# Read_Time_sensor_Tho_AMT_V2_0.net
KiCad netlist of a schematic drawn in Altium Designer
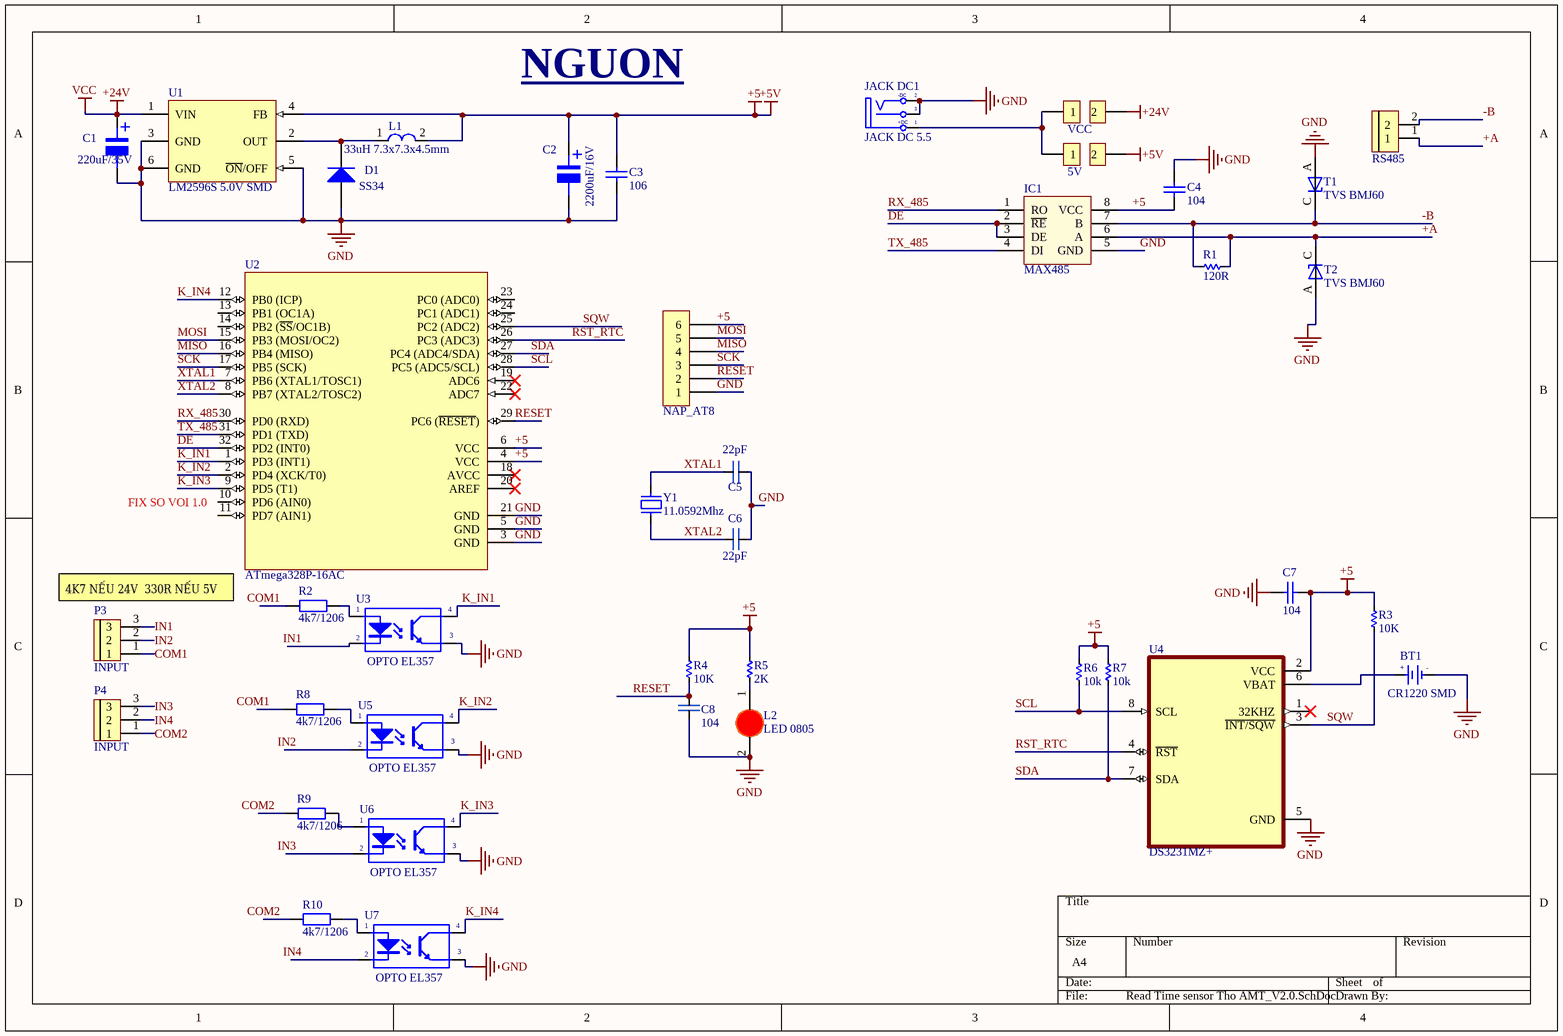
[diagram p0: Read Time sensor Tho AMT_V2.0.SchDoc]

(export (version "E")
  (design (tool "Eeschema 10.0.6"))
  (components
    (comp (ref "BT1")
      (value "CR1220 SMD")
      (footprint "DE PIN CR1220")
      (libsource (lib "NGUYEN VAN ANH HaUI") (part "De pin CR1220 SMD"))
    )
    (comp (ref "C1")
      (value "220uF/35V")
      (footprint "tu nhom 10 (g)")
      (description "Dán 35V")
      (libsource (lib "Altium_Lib_by_KhueNguyenCreator") (part "Tu Nhom 220uF 50V"))
    )
    (comp (ref "C2")
      (value "2200uF/16V")
      (footprint "tu nhom 6.3 (d)")
      (description "Dán")
      (libsource (lib "Altium_Lib_by_KhueNguyenCreator") (part "Tu Nhom 10uF 20V"))
    )
    (comp (ref "C3")
      (value "106")
      (footprint "tu 0805")
      (description "Dán")
      (libsource (lib "Altium_Lib_by_KhueNguyenCreator") (part "Tu 0805 105 50V 10%"))
    )
    (comp (ref "C4")
      (value "104")
      (footprint "TU 0805")
      (description "Dán")
      (libsource (lib "Altium_Lib_by_KhueNguyenCreator") (part "Tu 0805 104 50V 10%"))
    )
    (comp (ref "C5")
      (value "22pF")
      (footprint "TU 0805")
      (libsource (lib "NGUYEN VAN ANH HaUI") (part "TU 0805"))
    )
    (comp (ref "C6")
      (value "22pF")
      (footprint "TU 0805")
      (libsource (lib "NGUYEN VAN ANH HaUI") (part "TU 0805"))
    )
    (comp (ref "C7")
      (value "104")
      (footprint "TU 0805")
      (description "Dán")
      (libsource (lib "Altium_Lib_by_KhueNguyenCreator") (part "Tu 0805 104 50V 10%"))
    )
    (comp (ref "C8")
      (value "104")
      (footprint "TU 0805")
      (libsource (lib "NGUYEN VAN ANH HaUI") (part "TU 0805"))
    )
    (comp (ref "D1")
      (value "SS34")
      (footprint "DIODE SMA")
      (description "Dán")
      (libsource (lib "Altium_Lib_by_KhueNguyenCreator") (part "Diode SS14 ( 1N5819)"))
    )
    (comp (ref "EDG 1")
      (value "RS485")
      (footprint "CON 2 2EDG5.08")
      (description "Cắm")
      (libsource (lib "Altium_Lib_by_KhueNguyenCreator") (part "CON 2 EDG5.08"))
    )
    (comp (ref "H1")
      (value "NAP_AT8")
      (footprint "Header 6P DC 2.54")
      (description "Cắm")
      (libsource (lib "Altium_Lib_by_KhueNguyenCreator") (part "Header 6P 2.54 Duc Cong"))
    )
    (comp (ref "IC1")
      (value "MAX485")
      (footprint "SO8")
      (description "RS232 - RS485 (Same sn75176)")
      (libsource (lib "Cty1") (part "MAX485"))
    )
    (comp (ref "JACK DC1")
      (value "JACK DC 5.5")
      (footprint "JACK DC 5.5")
      (libsource (lib "NGUYEN VAN ANH HaUI") (part "JACK DC 5.5"))
    )
    (comp (ref "L1")
      (value "33uH 7.3x7.3x4.5mm")
      (footprint "L-SMD-M-7.3x4.5")
      (fields
        (field (name "PARTNO") "78477010")
        (field (name "MANUFACTURER") "Wurth Elektronik")
        (field (name "CREATED BY") "Baojun Chen")
      )
      (libsource (lib "NGUYEN VAN ANH HaUI") (part "L-SMD-1"))
    )
    (comp (ref "L2")
      (value "LED 0805")
      (footprint "LED-0805-Red")
      (description "Dán")
      (libsource (lib "Altium_Lib_by_KhueNguyenCreator") (part "LED 0805 Do"))
    )
    (comp (ref "P1")
      (value "VCC")
      (footprint "SMT-0805-RES")
      (libsource (lib "NGUYEN VAN ANH HaUI") (part "Pad han noi 2 duong"))
    )
    (comp (ref "P2")
      (value "5V")
      (footprint "SMT-0805-RES")
      (libsource (lib "NGUYEN VAN ANH HaUI") (part "Pad han noi 2 duong"))
    )
    (comp (ref "P3")
      (value "INPUT")
      (footprint "CON 3 3EDG5.08")
      (description "Cắm")
      (libsource (lib "NGUYEN VAN ANH HaUI") (part "CON 3 EDG5.08"))
    )
    (comp (ref "P4")
      (value "INPUT")
      (footprint "CON 3 3EDG5.08")
      (description "Cắm")
      (libsource (lib "NGUYEN VAN ANH HaUI") (part "CON 3 EDG5.08"))
    )
    (comp (ref "R1")
      (value "120R")
      (footprint "RES-SMD-0805")
      (description "Resistor")
      (fields
        (field (name "MANUFACTURER") "Generic Components")
        (field (name "PUBLISHER") "Altium Hobart Technology Centre")
      )
      (libsource (lib "NGUYEN VAN ANH HaUI") (part "Res-SMD"))
    )
    (comp (ref "R2")
      (value "4k7/1206")
      (footprint "tro smd 1206")
      (description "Dán")
      (libsource (lib "NGUYEN VAN ANH HaUI") (part "Tro 0805 5% 10k"))
    )
    (comp (ref "R3")
      (value "10K")
      (footprint "RES-SMD-0805")
      (description "Resistor")
      (fields
        (field (name "MANUFACTURER") "Generic Components")
        (field (name "PUBLISHER") "Altium Hobart Technology Centre")
      )
      (libsource (lib "NGUYEN VAN ANH HaUI") (part "Res-SMD"))
    )
    (comp (ref "R4")
      (value "10K")
      (footprint "RES-SMD-0805")
      (description "Resistor")
      (fields
        (field (name "MANUFACTURER") "Generic Components")
        (field (name "PUBLISHER") "Altium Hobart Technology Centre")
      )
      (libsource (lib "NGUYEN VAN ANH HaUI") (part "Res-SMD"))
    )
    (comp (ref "R5")
      (value "2K")
      (footprint "RES-SMD-0805")
      (description "Resistor")
      (fields
        (field (name "MANUFACTURER") "Generic Components")
        (field (name "PUBLISHER") "Altium Hobart Technology Centre")
      )
      (libsource (lib "NGUYEN VAN ANH HaUI") (part "Res-SMD"))
    )
    (comp (ref "R6")
      (value "10k")
      (footprint "RES-SMD-0805")
      (description "Resistor")
      (fields
        (field (name "MANUFACTURER") "Generic Components")
        (field (name "PUBLISHER") "Altium Hobart Technology Centre")
      )
      (libsource (lib "NGUYEN VAN ANH HaUI") (part "Res-SMD"))
    )
    (comp (ref "R7")
      (value "10k")
      (footprint "RES-SMD-0805")
      (description "Resistor")
      (fields
        (field (name "MANUFACTURER") "Generic Components")
        (field (name "PUBLISHER") "Altium Hobart Technology Centre")
      )
      (libsource (lib "NGUYEN VAN ANH HaUI") (part "Res-SMD"))
    )
    (comp (ref "R8")
      (value "4k7/1206")
      (footprint "tro smd 1206")
      (description "Dán")
      (libsource (lib "NGUYEN VAN ANH HaUI") (part "Tro 0805 5% 10k"))
    )
    (comp (ref "R9")
      (value "4k7/1206")
      (footprint "tro smd 1206")
      (description "Dán")
      (libsource (lib "NGUYEN VAN ANH HaUI") (part "Tro 0805 5% 10k"))
    )
    (comp (ref "R10")
      (value "4k7/1206")
      (footprint "tro smd 1206")
      (description "Dán")
      (libsource (lib "NGUYEN VAN ANH HaUI") (part "Tro 0805 5% 10k"))
    )
    (comp (ref "T1")
      (value "TVS BMJ60")
      (footprint "TVS BMJ60")
      (libsource (lib "NGUYEN VAN ANH HaUI") (part "TVS BMJ60"))
    )
    (comp (ref "T2")
      (value "TVS BMJ60")
      (footprint "TVS BMJ60")
      (libsource (lib "NGUYEN VAN ANH HaUI") (part "TVS BMJ60"))
    )
    (comp (ref "U1")
      (value "LM2596S 5.0V SMD")
      (footprint "TO263-5")
      (description "Dán")
      (libsource (lib "Altium_Lib_by_KhueNguyenCreator") (part "LM2576HVS 5.0V SMD"))
    )
    (comp (ref "U2")
      (value "ATmega328P-16AC")
      (footprint "32A_N")
      (description "8-Bit AVR Microcontroller with 8K Bytes of In-System Programmable Flash Memory")
      (fields (field (name "PUBLISHER") "Altium Limited"))
      (libsource (lib "Atmel Microcontroller 8-Bit AVR") (part "ATmega8-16AC"))
    )
    (comp (ref "U3")
      (value "OPTO EL357")
      (footprint "OPTO EL354")
      (description "Single Opto")
      (libsource (lib "NGUYEN VAN ANH HaUI") (part "OPTO PC817 SMD"))
    )
    (comp (ref "U4")
      (value "DS3231MZ+")
      (footprint "SOIC-8")
      (fields (field (name "MF") "Analog Devices"))
      (libsource (lib "VIN_HW") (part "DS3231MZ+"))
    )
    (comp (ref "U5")
      (value "OPTO EL357")
      (footprint "OPTO EL354")
      (description "Single Opto")
      (libsource (lib "NGUYEN VAN ANH HaUI") (part "OPTO PC817 SMD"))
    )
    (comp (ref "U6")
      (value "OPTO EL357")
      (footprint "OPTO EL354")
      (description "Single Opto")
      (libsource (lib "NGUYEN VAN ANH HaUI") (part "OPTO PC817 SMD"))
    )
    (comp (ref "U7")
      (value "OPTO EL357")
      (footprint "OPTO EL354")
      (description "Single Opto")
      (libsource (lib "NGUYEN VAN ANH HaUI") (part "OPTO PC817 SMD"))
    )
    (comp (ref "Y1")
      (value "11.0592Mhz")
      (footprint "Thach Anh 2 chan SMD5032")
      (description "Crystal For all Crystal 2pin.")
      (libsource (lib "NGUYEN VAN ANH HaUI") (part "Thach Anh 2 chan SMD 5032"))
    )
  )
  (nets
    (net (code "1") (name "+5") (class "Default")
      (node (ref "C2") (pin "1") (pinfunction "1_1") (pintype "passive"))
      (node (ref "C3") (pin "2") (pinfunction "2_2") (pintype "passive"))
      (node (ref "C4") (pin "1") (pinfunction "1_1") (pintype "passive"))
      (node (ref "C7") (pin "1") (pinfunction "1_1") (pintype "passive"))
      (node (ref "H1") (pin "6") (pinfunction "6_6") (pintype "passive"))
      (node (ref "IC1") (pin "8") (pinfunction "VCC_8") (pintype "passive"))
      (node (ref "L1") (pin "2") (pinfunction "2_2") (pintype "passive"))
      (node (ref "P2") (pin "2") (pinfunction "2_2") (pintype "passive"))
      (node (ref "R3") (pin "1") (pinfunction "1_1") (pintype "passive"))
      (node (ref "R4") (pin "2") (pinfunction "2_2") (pintype "passive"))
      (node (ref "R5") (pin "1") (pinfunction "1_1") (pintype "passive"))
      (node (ref "R6") (pin "1") (pinfunction "1_1") (pintype "passive"))
      (node (ref "R7") (pin "1") (pinfunction "1_1") (pintype "passive"))
      (node (ref "U1") (pin "4") (pinfunction "FB_4") (pintype "input"))
      (node (ref "U2") (pin "4") (pinfunction "VCC_4") (pintype "power_in"))
      (node (ref "U2") (pin "6") (pinfunction "VCC_6") (pintype "power_in"))
      (node (ref "U4") (pin "2") (pinfunction "VCC_2") (pintype "power_in"))
    )
    (net (code "2") (name "+24V") (class "Default")
      (node (ref "C1") (pin "1") (pinfunction "1_1") (pintype "passive"))
      (node (ref "P1") (pin "2") (pinfunction "2_2") (pintype "passive"))
      (node (ref "U1") (pin "1") (pinfunction "VIN_1") (pintype "power_in"))
    )
    (net (code "3") (name "/+A") (class "Default")
      (node (ref "EDG 1") (pin "1") (pinfunction "1_1") (pintype "passive"))
      (node (ref "IC1") (pin "6") (pinfunction "A_6") (pintype "passive"))
      (node (ref "R1") (pin "2") (pinfunction "2_2") (pintype "passive"))
      (node (ref "T2") (pin "C") (pinfunction "C_C") (pintype "passive"))
    )
    (net (code "4") (name "/-B") (class "Default")
      (node (ref "EDG 1") (pin "2") (pinfunction "2_2") (pintype "passive"))
      (node (ref "IC1") (pin "7") (pinfunction "B_7") (pintype "passive"))
      (node (ref "R1") (pin "1") (pinfunction "1_1") (pintype "passive"))
      (node (ref "T1") (pin "C") (pinfunction "C_C") (pintype "passive"))
    )
    (net (code "5") (name "/COM1") (class "Default")
      (node (ref "P3") (pin "1") (pinfunction "1_1") (pintype "passive"))
      (node (ref "R2") (pin "1") (pinfunction "1_1") (pintype "passive"))
      (node (ref "R8") (pin "1") (pinfunction "1_1") (pintype "passive"))
    )
    (net (code "6") (name "/COM2") (class "Default")
      (node (ref "P4") (pin "1") (pinfunction "1_1") (pintype "passive"))
      (node (ref "R10") (pin "1") (pinfunction "1_1") (pintype "passive"))
      (node (ref "R9") (pin "1") (pinfunction "1_1") (pintype "passive"))
    )
    (net (code "7") (name "/DE") (class "Default")
      (node (ref "IC1") (pin "2") (pinfunction "~{RE}_2") (pintype "passive"))
      (node (ref "IC1") (pin "3") (pinfunction "DE_3") (pintype "passive"))
      (node (ref "U2") (pin "32") (pinfunction "PD2_(INT0)_32") (pintype "bidirectional"))
    )
    (net (code "8") (name "/IN1") (class "Default")
      (node (ref "P3") (pin "3") (pinfunction "3_3") (pintype "passive"))
      (node (ref "U3") (pin "2") (pinfunction "K_2") (pintype "passive"))
    )
    (net (code "9") (name "/IN2") (class "Default")
      (node (ref "P3") (pin "2") (pinfunction "2_2") (pintype "passive"))
      (node (ref "U5") (pin "2") (pinfunction "K_2") (pintype "passive"))
    )
    (net (code "10") (name "/IN3") (class "Default")
      (node (ref "P4") (pin "3") (pinfunction "3_3") (pintype "passive"))
      (node (ref "U6") (pin "2") (pinfunction "K_2") (pintype "passive"))
    )
    (net (code "11") (name "/IN4") (class "Default")
      (node (ref "P4") (pin "2") (pinfunction "2_2") (pintype "passive"))
      (node (ref "U7") (pin "2") (pinfunction "K_2") (pintype "passive"))
    )
    (net (code "12") (name "/K_IN1") (class "Default")
      (node (ref "U2") (pin "1") (pinfunction "PD3_(INT1)_1") (pintype "bidirectional"))
      (node (ref "U3") (pin "4") (pinfunction "C_4") (pintype "passive"))
    )
    (net (code "13") (name "/K_IN2") (class "Default")
      (node (ref "U2") (pin "2") (pinfunction "PD4_(XCK/T0)_2") (pintype "bidirectional"))
      (node (ref "U5") (pin "4") (pinfunction "C_4") (pintype "passive"))
    )
    (net (code "14") (name "/K_IN3") (class "Default")
      (node (ref "U2") (pin "9") (pinfunction "PD5_(T1)_9") (pintype "bidirectional"))
      (node (ref "U6") (pin "4") (pinfunction "C_4") (pintype "passive"))
    )
    (net (code "15") (name "/K_IN4") (class "Default")
      (node (ref "U2") (pin "12") (pinfunction "PB0_(ICP)_12") (pintype "bidirectional"))
      (node (ref "U7") (pin "4") (pinfunction "C_4") (pintype "passive"))
    )
    (net (code "16") (name "/MISO") (class "Default")
      (node (ref "H1") (pin "4") (pinfunction "4_4") (pintype "passive"))
      (node (ref "U2") (pin "16") (pinfunction "PB4_(MISO)_16") (pintype "bidirectional"))
    )
    (net (code "17") (name "/MOSI") (class "Default")
      (node (ref "H1") (pin "5") (pinfunction "5_5") (pintype "passive"))
      (node (ref "U2") (pin "15") (pinfunction "PB3_(MOSI/OC2)_15") (pintype "bidirectional"))
    )
    (net (code "18") (name "/RESET") (class "Default")
      (node (ref "C8") (pin "1") (pinfunction "33_1") (pintype "passive"))
      (node (ref "H1") (pin "2") (pinfunction "2_2") (pintype "passive"))
      (node (ref "R4") (pin "1") (pinfunction "1_1") (pintype "passive"))
      (node (ref "U2") (pin "29") (pinfunction "PC6_(~{RESET})_29") (pintype "bidirectional"))
    )
    (net (code "19") (name "/RST_RTC") (class "Default")
      (node (ref "U2") (pin "26") (pinfunction "PC3_(ADC3)_26") (pintype "bidirectional"))
      (node (ref "U4") (pin "4") (pinfunction "~{RST}_4") (pintype "bidirectional"))
    )
    (net (code "20") (name "/RX_485") (class "Default")
      (node (ref "IC1") (pin "1") (pinfunction "RO_1") (pintype "passive"))
      (node (ref "U2") (pin "30") (pinfunction "PD0_(RXD)_30") (pintype "bidirectional"))
    )
    (net (code "21") (name "/SCK") (class "Default")
      (node (ref "H1") (pin "3") (pinfunction "3_3") (pintype "passive"))
      (node (ref "U2") (pin "17") (pinfunction "PB5_(SCK)_17") (pintype "bidirectional"))
    )
    (net (code "22") (name "/SCL") (class "Default")
      (node (ref "R6") (pin "2") (pinfunction "2_2") (pintype "passive"))
      (node (ref "U2") (pin "28") (pinfunction "PC5_(ADC5/SCL)_28") (pintype "bidirectional"))
      (node (ref "U4") (pin "8") (pinfunction "SCL_8") (pintype "input"))
    )
    (net (code "23") (name "/SDA") (class "Default")
      (node (ref "R7") (pin "2") (pinfunction "2_2") (pintype "passive"))
      (node (ref "U2") (pin "27") (pinfunction "PC4_(ADC4/SDA)_27") (pintype "bidirectional"))
      (node (ref "U4") (pin "7") (pinfunction "SDA_7") (pintype "bidirectional"))
    )
    (net (code "24") (name "/SQW") (class "Default")
      (node (ref "R3") (pin "2") (pinfunction "2_2") (pintype "passive"))
      (node (ref "U2") (pin "25") (pinfunction "PC2_(ADC2)_25") (pintype "bidirectional"))
      (node (ref "U4") (pin "3") (pinfunction "~{INT/SQW}_3") (pintype "output"))
    )
    (net (code "25") (name "/TX_485") (class "Default")
      (node (ref "IC1") (pin "4") (pinfunction "DI_4") (pintype "passive"))
      (node (ref "U2") (pin "31") (pinfunction "PD1_(TXD)_31") (pintype "bidirectional"))
    )
    (net (code "26") (name "/XTAL1") (class "Default")
      (node (ref "C5") (pin "1") (pinfunction "33_1") (pintype "passive"))
      (node (ref "U2") (pin "7") (pinfunction "PB6_(XTAL1/TOSC1)_7") (pintype "bidirectional"))
      (node (ref "Y1") (pin "2") (pinfunction "2_2") (pintype "passive"))
    )
    (net (code "27") (name "/XTAL2") (class "Default")
      (node (ref "C6") (pin "1") (pinfunction "33_1") (pintype "passive"))
      (node (ref "U2") (pin "8") (pinfunction "PB7_(XTAL2/TOSC2)_8") (pintype "bidirectional"))
      (node (ref "Y1") (pin "1") (pinfunction "1_1") (pintype "passive"))
    )
    (net (code "28") (name "GND") (class "Default")
      (node (ref "BT1") (pin "2") (pinfunction "GND_2") (pintype "passive"))
      (node (ref "C1") (pin "2") (pinfunction "2_2") (pintype "passive"))
      (node (ref "C2") (pin "2") (pinfunction "2_2") (pintype "passive"))
      (node (ref "C3") (pin "1") (pinfunction "1_1") (pintype "passive"))
      (node (ref "C4") (pin "2") (pinfunction "2_2") (pintype "passive"))
      (node (ref "C5") (pin "2") (pinfunction "2_2") (pintype "passive"))
      (node (ref "C6") (pin "2") (pinfunction "2_2") (pintype "passive"))
      (node (ref "C7") (pin "2") (pinfunction "2_2") (pintype "passive"))
      (node (ref "C8") (pin "2") (pinfunction "2_2") (pintype "passive"))
      (node (ref "D1") (pin "1") (pinfunction "A_1") (pintype "passive"))
      (node (ref "H1") (pin "1") (pinfunction "1_1") (pintype "passive"))
      (node (ref "IC1") (pin "5") (pinfunction "GND_5") (pintype "passive"))
      (node (ref "JACK DC1") (pin "2") (pinfunction "TN_2") (pintype "passive"))
      (node (ref "JACK DC1") (pin "3") (pinfunction "S_3") (pintype "power_in"))
      (node (ref "L2") (pin "2") (pinfunction "K_2") (pintype "passive"))
      (node (ref "T1") (pin "A") (pinfunction "A_A") (pintype "passive"))
      (node (ref "T2") (pin "A") (pinfunction "A_A") (pintype "passive"))
      (node (ref "U1") (pin "3") (pinfunction "GND_3") (pintype "power_in"))
      (node (ref "U1") (pin "5") (pinfunction "~{ON}/OFF_5") (pintype "input"))
      (node (ref "U1") (pin "6") (pinfunction "GND_6") (pintype "passive"))
      (node (ref "U2") (pin "21") (pinfunction "GND_21") (pintype "power_in"))
      (node (ref "U2") (pin "3") (pinfunction "GND_3") (pintype "power_in"))
      (node (ref "U2") (pin "5") (pinfunction "GND_5") (pintype "power_in"))
      (node (ref "U3") (pin "3") (pinfunction "E_3") (pintype "passive"))
      (node (ref "U4") (pin "5") (pinfunction "GND_5") (pintype "power_in"))
      (node (ref "U5") (pin "3") (pinfunction "E_3") (pintype "passive"))
      (node (ref "U6") (pin "3") (pinfunction "E_3") (pintype "passive"))
      (node (ref "U7") (pin "3") (pinfunction "E_3") (pintype "passive"))
    )
    (net (code "29") (name "Net-(BT1-+3V)") (class "Default")
      (node (ref "BT1") (pin "1") (pinfunction "+3V_1") (pintype "passive"))
      (node (ref "U4") (pin "6") (pinfunction "VBAT_6") (pintype "power_in"))
    )
    (net (code "30") (name "Net-(D1-K)") (class "Default")
      (node (ref "D1") (pin "2") (pinfunction "K_2") (pintype "passive"))
      (node (ref "L1") (pin "1") (pinfunction "1_1") (pintype "passive"))
      (node (ref "U1") (pin "2") (pinfunction "OUT_2") (pintype "power_in"))
    )
    (net (code "31") (name "Net-(JACK DC1-T)") (class "Default")
      (node (ref "JACK DC1") (pin "1") (pinfunction "T_1") (pintype "passive"))
      (node (ref "P1") (pin "1") (pinfunction "1_1") (pintype "passive"))
      (node (ref "P2") (pin "1") (pinfunction "1_1") (pintype "passive"))
    )
    (net (code "32") (name "Net-(L2-A)") (class "Default")
      (node (ref "L2") (pin "1") (pinfunction "A_1") (pintype "passive"))
      (node (ref "R5") (pin "2") (pinfunction "2_2") (pintype "passive"))
    )
    (net (code "33") (name "Net-(U3-A)") (class "Default")
      (node (ref "R2") (pin "2") (pinfunction "2_2") (pintype "passive"))
      (node (ref "U3") (pin "1") (pinfunction "A_1") (pintype "passive"))
    )
    (net (code "34") (name "Net-(U5-A)") (class "Default")
      (node (ref "R8") (pin "2") (pinfunction "2_2") (pintype "passive"))
      (node (ref "U5") (pin "1") (pinfunction "A_1") (pintype "passive"))
    )
    (net (code "35") (name "Net-(U6-A)") (class "Default")
      (node (ref "R9") (pin "2") (pinfunction "2_2") (pintype "passive"))
      (node (ref "U6") (pin "1") (pinfunction "A_1") (pintype "passive"))
    )
    (net (code "36") (name "Net-(U7-A)") (class "Default")
      (node (ref "R10") (pin "2") (pinfunction "2_2") (pintype "passive"))
      (node (ref "U7") (pin "1") (pinfunction "A_1") (pintype "passive"))
    )
    (net (code "37") (name "unconnected-(U2-ADC6-Pad19)") (class "Default")
      (node (ref "U2") (pin "19") (pinfunction "ADC6_19") (pintype "input+no_connect"))
    )
    (net (code "38") (name "unconnected-(U2-ADC7-Pad22)") (class "Default")
      (node (ref "U2") (pin "22") (pinfunction "ADC7_22") (pintype "input+no_connect"))
    )
    (net (code "39") (name "unconnected-(U2-AREF-Pad20)") (class "Default")
      (node (ref "U2") (pin "20") (pinfunction "AREF_20") (pintype "passive+no_connect"))
    )
    (net (code "40") (name "unconnected-(U2-AVCC-Pad18)") (class "Default")
      (node (ref "U2") (pin "18") (pinfunction "AVCC_18") (pintype "power_in+no_connect"))
    )
    (net (code "41") (name "unconnected-(U2-PB1_(OC1A)-Pad13)") (class "Default")
      (node (ref "U2") (pin "13") (pinfunction "PB1_(OC1A)_13") (pintype "bidirectional"))
    )
    (net (code "42") (name "unconnected-(U2-PB2_(~{SS}{slash}OC1B)-Pad14)") (class "Default")
      (node (ref "U2") (pin "14") (pinfunction "PB2_(~{SS}/OC1B)_14") (pintype "bidirectional"))
    )
    (net (code "43") (name "unconnected-(U2-PC0_(ADC0)-Pad23)") (class "Default")
      (node (ref "U2") (pin "23") (pinfunction "PC0_(ADC0)_23") (pintype "bidirectional"))
    )
    (net (code "44") (name "unconnected-(U2-PC1_(ADC1)-Pad24)") (class "Default")
      (node (ref "U2") (pin "24") (pinfunction "PC1_(ADC1)_24") (pintype "bidirectional"))
    )
    (net (code "45") (name "unconnected-(U2-PD6_(AIN0)-Pad10)") (class "Default")
      (node (ref "U2") (pin "10") (pinfunction "PD6_(AIN0)_10") (pintype "bidirectional"))
    )
    (net (code "46") (name "unconnected-(U2-PD7_(AIN1)-Pad11)") (class "Default")
      (node (ref "U2") (pin "11") (pinfunction "PD7_(AIN1)_11") (pintype "bidirectional"))
    )
    (net (code "47") (name "unconnected-(U4-32KHZ-Pad1)") (class "Default")
      (node (ref "U4") (pin "1") (pinfunction "32KHZ_1") (pintype "output+no_connect"))
    )
  )
)
